# temp1.net
KiCad netlist of a schematic drawn in Altium Designer
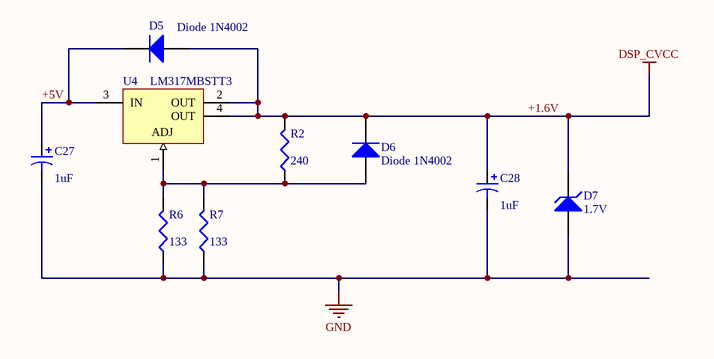
[diagram p0: temp1.SchDoc]

(export (version "E")
  (design (tool "Eeschema 10.0.6"))
  (components
    (comp (ref "C27")
      (value "1uF")
      (footprint "1812")
      (description "Polarized Capacitor (Surface Mount)")
      (fields (field (name "Comment") "Cap Pol3") (field (name "PUBLISHER") "Altium Limited"))
      (libsource (lib "Miscellaneous Devices") (part "Cap Pol3"))
    )
    (comp (ref "C28")
      (value "1uF")
      (footprint "1812")
      (description "Polarized Capacitor (Surface Mount)")
      (fields (field (name "Comment") "Cap Pol3") (field (name "PUBLISHER") "Altium Limited"))
      (libsource (lib "Miscellaneous Devices") (part "Cap Pol3"))
    )
    (comp (ref "D5")
      (value "Diode 1N4002")
      (footprint "DO-41")
      (description "1 Amp General Purpose Rectifier")
      (fields (field (name "PUBLISHER") "Altium Limited"))
      (libsource (lib "Miscellaneous Devices") (part "Diode 1N4002"))
    )
    (comp (ref "D6")
      (value "Diode 1N4002")
      (footprint "DO-41")
      (description "1 Amp General Purpose Rectifier")
      (fields (field (name "PUBLISHER") "Altium Limited"))
      (libsource (lib "Miscellaneous Devices") (part "Diode 1N4002"))
    )
    (comp (ref "D7")
      (value "1.7V")
      (footprint "DL-41")
      (description "Silicon Zener Diode")
      (fields (field (name "PUBLISHER") "Altium Limited"))
      (libsource (lib "Vishay Lite-On Discrete Diode") (part "DL4742A"))
    )
    (comp (ref "R2")
      (value "240")
      (footprint "3225[1210]")
      (description "Resistor")
      (fields (field (name "Comment") "Res3") (field (name "PUBLISHER") "Altium Limited"))
      (libsource (lib "Miscellaneous Devices") (part "Res3"))
    )
    (comp (ref "R6")
      (value "133")
      (footprint "3225[1210]")
      (description "Resistor")
      (fields (field (name "Comment") "Res3") (field (name "PUBLISHER") "Altium Limited"))
      (libsource (lib "Miscellaneous Devices") (part "Res3"))
    )
    (comp (ref "R7")
      (value "133")
      (footprint "3225[1210]")
      (description "Resistor")
      (fields (field (name "Comment") "Res3") (field (name "PUBLISHER") "Altium Limited"))
      (libsource (lib "Miscellaneous Devices") (part "Res3"))
    )
    (comp (ref "U4")
      (value "LM317MBSTT3")
      (footprint "318E-04")
      (description "Three-Terminal Adjustable Output Positive Voltage Regulator")
      (fields (field (name "PUBLISHER") "Altium Limited"))
      (libsource (lib "ON Semi Power Mgt Voltage Regulator") (part "LM317MBSTT3"))
    )
  )
  (nets
    (net (code "1") (name "/+5V") (class "Default")
      (node (ref "C27") (pin "1") (pinfunction "1_1") (pintype "passive"))
      (node (ref "D5") (pin "2") (pinfunction "K_2") (pintype "passive"))
      (node (ref "U4") (pin "3") (pinfunction "IN_3") (pintype "power_in"))
    )
    (net (code "2") (name "DSP_CVCC") (class "Default")
      (node (ref "C28") (pin "1") (pinfunction "1_1") (pintype "passive"))
      (node (ref "D5") (pin "1") (pinfunction "A_1") (pintype "passive"))
      (node (ref "D6") (pin "2") (pinfunction "K_2") (pintype "passive"))
      (node (ref "D7") (pin "2") (pinfunction "K_2") (pintype "passive"))
      (node (ref "R2") (pin "2") (pinfunction "2_2") (pintype "passive"))
      (node (ref "U4") (pin "2") (pinfunction "OUT_2") (pintype "power_in"))
      (node (ref "U4") (pin "4") (pinfunction "OUT_4") (pintype "power_in"))
    )
    (net (code "3") (name "GND") (class "Default")
      (node (ref "C27") (pin "2") (pinfunction "2_2") (pintype "passive"))
      (node (ref "C28") (pin "2") (pinfunction "2_2") (pintype "passive"))
      (node (ref "D7") (pin "1") (pinfunction "A_1") (pintype "passive"))
      (node (ref "R6") (pin "1") (pinfunction "1_1") (pintype "passive"))
      (node (ref "R7") (pin "1") (pinfunction "1_1") (pintype "passive"))
    )
    (net (code "4") (name "Net-(D6-A)") (class "Default")
      (node (ref "D6") (pin "1") (pinfunction "A_1") (pintype "passive"))
      (node (ref "R2") (pin "1") (pinfunction "1_1") (pintype "passive"))
      (node (ref "R6") (pin "2") (pinfunction "2_2") (pintype "passive"))
      (node (ref "R7") (pin "2") (pinfunction "2_2") (pintype "passive"))
      (node (ref "U4") (pin "1") (pinfunction "ADJ_1") (pintype "input"))
    )
  )
)
